# Altium-Sheet_1_2023-12-20.net
KiCad netlist of a schematic drawn in Altium Designer
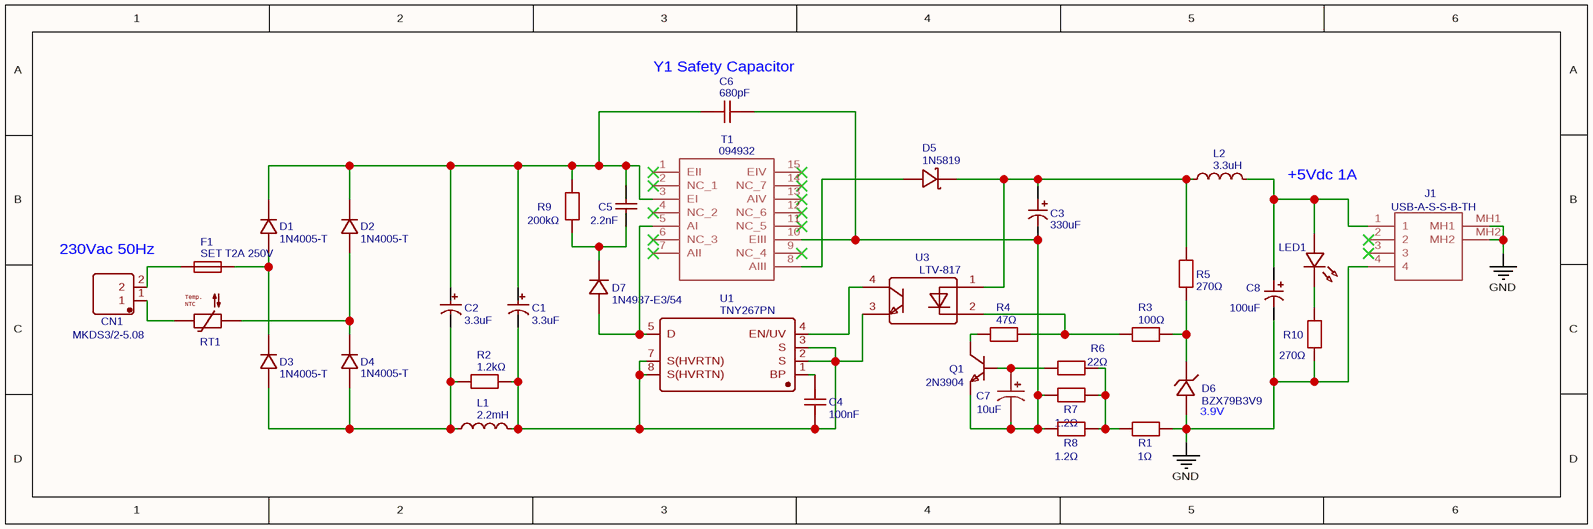
[diagram p0: Altium-Sheet_1_2023-12-20.schdoc]

(export (version "E")
  (design (tool "Eeschema 10.0.6"))
  (components
    (comp (ref "C1")
      (value "3.3uF")
      (fields
        (field (name "MANUFACTURER") "CX(承兴)")
        (field (name "MANUFACTURER PART") "KM335M400F12RR0VH2FP0")
      )
      (libsource (lib "altium-import") (part "root_3_3.3uF_"))
    )
    (comp (ref "C2")
      (value "3.3uF")
      (fields
        (field (name "MANUFACTURER") "CX(承兴)")
        (field (name "MANUFACTURER PART") "KM335M400F12RR0VH2FP0")
      )
      (libsource (lib "altium-import") (part "root_3_3.3uF_"))
    )
    (comp (ref "C3")
      (value "330uF")
      (fields
        (field (name "MANUFACTURER") "PANASONIC(松下)")
        (field (name "MANUFACTURER PART") "EEU-FM1V331")
        (field (name "CONTRIBUTOR") "lcsc")
      )
      (libsource (lib "altium-import") (part "root_3_330uF_"))
    )
    (comp (ref "C4")
      (value "100nF")
      (fields
        (field (name "MANUFACTURER") "KNSCHA(科尼盛)")
        (field (name "MANUFACTURER PART") "178MU0002")
        (field (name "CONTRIBUTOR") "lcsc")
      )
      (libsource (lib "altium-import") (part "root_1_100nF_"))
    )
    (comp (ref "C5") (value "2.2nF") (libsource (lib "altium-import") (part "root_1_2.2nF_")))
    (comp (ref "C6")
      (value "680pF")
      (fields
        (field (name "MANUFACTURER") "VISHAY(威世)")
        (field (name "MANUFACTURER PART") "AY1222M47Y5UC63L0")
        (field (name "CONTRIBUTOR") "LCSC")
      )
      (libsource (lib "altium-import") (part "root_0_680pF_"))
    )
    (comp (ref "C7")
      (value "10uF")
      (fields
        (field (name "MANUFACTURER") "rubycon(红宝石)")
        (field (name "MANUFACTURER PART") "10MS510MEFC4X5")
        (field (name "CONTRIBUTOR") "lcsc")
      )
      (libsource (lib "altium-import") (part "root_3_10uF_"))
    )
    (comp (ref "C8")
      (value "100uF")
      (fields
        (field (name "MANUFACTURER") "ELNA(伊娜)")
        (field (name "MANUFACTURER PART") "RFO-25V101MF3P#-T58")
        (field (name "CONTRIBUTOR") "lcsc")
      )
      (libsource (lib "altium-import") (part "root_3_100uF_"))
    )
    (comp (ref "CN1")
      (value "MKDS3/2-5.08")
      (fields
        (field (name "MANUFACTURER") "Phoenix Contact(菲尼克斯)")
        (field (name "MANUFACTURER PART") "1711725")
      )
      (libsource (lib "altium-import") (part "root_2_MKDS3/2-5.08_"))
    )
    (comp (ref "D1")
      (value "1N4005-T")
      (fields (field (name "MANUFACTURER") "DIODES(美台)") (field (name "CONTRIBUTOR") "LCSC"))
      (libsource (lib "altium-import") (part "root_3_1N4005-T_"))
    )
    (comp (ref "D2")
      (value "1N4005-T")
      (fields (field (name "MANUFACTURER") "DIODES(美台)") (field (name "CONTRIBUTOR") "LCSC"))
      (libsource (lib "altium-import") (part "root_3_1N4005-T_"))
    )
    (comp (ref "D3")
      (value "1N4005-T")
      (fields (field (name "MANUFACTURER") "DIODES(美台)") (field (name "CONTRIBUTOR") "LCSC"))
      (libsource (lib "altium-import") (part "root_3_1N4005-T_"))
    )
    (comp (ref "D4")
      (value "1N4005-T")
      (fields (field (name "MANUFACTURER") "DIODES(美台)") (field (name "CONTRIBUTOR") "LCSC"))
      (libsource (lib "altium-import") (part "root_3_1N4005-T_"))
    )
    (comp (ref "D5")
      (value "1N5819")
      (fields (field (name "MANUFACTURER") "ST(意法半导体)"))
      (libsource (lib "altium-import") (part "root_2_1N5819_"))
    )
    (comp (ref "D6")
      (value "BZX79B3V9")
      (fields
        (field (name "MANUFACTURER") "onsemi(安森美)")
        (field (name "MANUFACTURER PART") "1N5921BG")
        (field (name "CONTRIBUTOR") "LCSC")
      )
      (libsource (lib "altium-import") (part "root_0_BZX79B3V9_"))
    )
    (comp (ref "D7")
      (value "1N4937-E3/54")
      (fields (field (name "MANUFACTURER") "VISHAY(威世)") (field (name "CONTRIBUTOR") "LCSC"))
      (libsource (lib "altium-import") (part "root_1_1N4937-E3/54_"))
    )
    (comp (ref "F1")
      (value "SET T2A 250V")
      (fields (field (name "MANUFACTURER") "CHEVRON(诚润电子）") (field (name "CONTRIBUTOR") "lcsc"))
      (libsource (lib "altium-import") (part "root_0_SET T2A 250V_"))
    )
    (comp (ref "J1")
      (value "USB-A-S-S-B-TH")
      (fields (field (name "CONTRIBUTOR") "andreafato"))
      (libsource (lib "altium-import") (part "root_0_USB-A-S-S-B-TH_"))
    )
    (comp (ref "L1")
      (value "2.2mH")
      (fields
        (field (name "MANUFACTURER") "PROD(谱罗德)")
        (field (name "MANUFACTURER PART") "PDPTAT0810-222K")
        (field (name "CONTRIBUTOR") "lcsc")
      )
      (libsource (lib "altium-import") (part "root_0_2.2mH_"))
    )
    (comp (ref "L2")
      (value "3.3uH")
      (fields (field (name "MANUFACTURER PART") "VLU1012-3R3MB") (field (name "CONTRIBUTOR") "LCSC"))
      (libsource (lib "altium-import") (part "root_0_3.3uH_"))
    )
    (comp (ref "LED1")
      (value "LED-TH-5mm_WHT")
      (fields (field (name "CONTRIBUTOR") "LCEDA_Lib"))
      (libsource (lib "altium-import") (part "root_3_LED-TH-5mm_WHT_"))
    )
    (comp (ref "Q1")
      (value "2N3904")
      (fields (field (name "MANUFACTURER") "JSMSEMI(杰盛微)") (field (name "CONTRIBUTOR") "LCSC"))
      (libsource (lib "altium-import") (part "root_0_2N3904_"))
    )
    (comp (ref "R1")
      (value "1Ω")
      (fields
        (field (name "MANUFACTURER") "Tyohm(幸亚电阻)")
        (field (name "MANUFACTURER PART") "RN1/2WS1RFT/B")
        (field (name "CONTRIBUTOR") "lcsc")
      )
      (libsource (lib "altium-import") (part "root_0_1Ω_"))
    )
    (comp (ref "R2")
      (value "1.2kΩ")
      (fields
        (field (name "MANUFACTURER") "VO(翔胜)")
        (field (name "MANUFACTURER PART") "CR1W-1K2±5%-6T63")
        (field (name "CONTRIBUTOR") "lcsc")
      )
      (libsource (lib "altium-import") (part "root_0_1.2kΩ_"))
    )
    (comp (ref "R3")
      (value "100Ω")
      (fields
        (field (name "MANUFACTURER") "VO(翔胜)")
        (field (name "MANUFACTURER PART") "CR1/4W-100Ω±5%-ST52")
        (field (name "CONTRIBUTOR") "lcsc")
      )
      (libsource (lib "altium-import") (part "root_0_100Ω_"))
    )
    (comp (ref "R4")
      (value "47Ω")
      (fields
        (field (name "MANUFACTURER") "VO(翔胜)")
        (field (name "MANUFACTURER PART") "CR1/4W-100Ω±5%-ST52")
        (field (name "CONTRIBUTOR") "lcsc")
      )
      (libsource (lib "altium-import") (part "root_2_47Ω_"))
    )
    (comp (ref "R5")
      (value "270Ω")
      (fields
        (field (name "MANUFACTURER") "VO(翔胜)")
        (field (name "MANUFACTURER PART") "CR1/4W-100Ω±5%-ST52")
        (field (name "CONTRIBUTOR") "lcsc")
      )
      (libsource (lib "altium-import") (part "root_3_270Ω_"))
    )
    (comp (ref "R6")
      (value "22Ω")
      (fields
        (field (name "MANUFACTURER") "VO(翔胜)")
        (field (name "MANUFACTURER PART") "CR1/4W-100Ω±5%-ST52")
        (field (name "CONTRIBUTOR") "lcsc")
      )
      (libsource (lib "altium-import") (part "root_0_22Ω_"))
    )
    (comp (ref "R7")
      (value "1.2Ω")
      (fields
        (field (name "MANUFACTURER") "YAGEO(国巨)")
        (field (name "MANUFACTURER PART") "MFR50SFTE52-1R21")
        (field (name "CONTRIBUTOR") "lcsc")
      )
      (libsource (lib "altium-import") (part "root_0_1.2Ω_"))
    )
    (comp (ref "R8")
      (value "1.2Ω")
      (fields
        (field (name "MANUFACTURER") "YAGEO(国巨)")
        (field (name "MANUFACTURER PART") "MFR50SFTE52-1R21")
        (field (name "CONTRIBUTOR") "lcsc")
      )
      (libsource (lib "altium-import") (part "root_0_1.2Ω_"))
    )
    (comp (ref "R9")
      (value "200kΩ")
      (fields
        (field (name "MANUFACTURER") "VO(翔胜)")
        (field (name "MANUFACTURER PART") "CR1/2W-220K±5%-XT52")
        (field (name "CONTRIBUTOR") "lcsc")
      )
      (libsource (lib "altium-import") (part "root_3_200kΩ_"))
    )
    (comp (ref "R10")
      (value "270Ω")
      (fields
        (field (name "MANUFACTURER") "VO(翔胜)")
        (field (name "MANUFACTURER PART") "CR1/4W-100Ω±5%-ST52")
        (field (name "CONTRIBUTOR") "lcsc")
      )
      (libsource (lib "altium-import") (part "root_3_270Ω_"))
    )
    (comp (ref "RT1")
      (value "NO")
      (fields
        (field (name "MANUFACTURER PART") "CL-120")
        (field (name "MANUFACTURER") "Amphenol Advanced Sensors")
        (field (name "CONTRIBUTOR") "Xperia BlueStacks")
      )
      (libsource (lib "altium-import") (part "root_0_NO_"))
    )
    (comp (ref "T1")
      (value "094932")
      (fields (field (name "CONTRIBUTOR") "andreafato"))
      (libsource (lib "altium-import") (part "root_0_094932_"))
    )
    (comp (ref "U1")
      (value "TNY267PN")
      (fields (field (name "MANUFACTURER") "Power Integrations(帕沃英蒂格盛)"))
      (libsource (lib "altium-import") (part "root_2_TNY267PN_"))
    )
    (comp (ref "U3")
      (value "LTV-817")
      (fields (field (name "MANUFACTURER") "LITEON(光宝)") (field (name "CONTRIBUTOR") "LCSC"))
      (libsource (lib "altium-import") (part "root_0_LTV-817_"))
    )
  )
  (nets
    (net (code "1") (name "GND") (class "Default")
      (node (ref "C8") (pin "2") (pinfunction "2_2") (pintype "passive"))
      (node (ref "D6") (pin "2") (pinfunction "A_2") (pintype "passive"))
      (node (ref "J1") (pin "4") (pinfunction "4_4") (pintype "passive"))
      (node (ref "J1") (pin "MH1") (pinfunction "MH1_MH1") (pintype "passive"))
      (node (ref "J1") (pin "MH2") (pinfunction "MH2_MH2") (pintype "passive"))
      (node (ref "R1") (pin "2") (pinfunction "2_2") (pintype "passive"))
      (node (ref "R10") (pin "2") (pinfunction "2_2") (pintype "passive"))
    )
    (net (code "2") (name "Net-(C1-Pad2)") (class "Default")
      (node (ref "C1") (pin "2") (pinfunction "2_2") (pintype "passive"))
      (node (ref "C4") (pin "1") (pinfunction "1_1") (pintype "passive"))
      (node (ref "L1") (pin "2") (pinfunction "2_2") (pintype "passive"))
      (node (ref "R2") (pin "2") (pinfunction "2_2") (pintype "passive"))
      (node (ref "U1") (pin "2") (pinfunction "S_2") (pintype "passive"))
      (node (ref "U1") (pin "3") (pinfunction "S_3") (pintype "passive"))
      (node (ref "U1") (pin "7") (pinfunction "S(HVRTN)_7") (pintype "passive"))
      (node (ref "U1") (pin "8") (pinfunction "S(HVRTN)_8") (pintype "passive"))
      (node (ref "U3") (pin "3") (pinfunction "3_3") (pintype "passive"))
    )
    (net (code "3") (name "Net-(C2-Pad2)") (class "Default")
      (node (ref "C2") (pin "2") (pinfunction "2_2") (pintype "passive"))
      (node (ref "D3") (pin "2") (pinfunction "2_2") (pintype "passive"))
      (node (ref "D4") (pin "2") (pinfunction "2_2") (pintype "passive"))
      (node (ref "L1") (pin "1") (pinfunction "1_1") (pintype "passive"))
      (node (ref "R2") (pin "1") (pinfunction "1_1") (pintype "passive"))
    )
    (net (code "4") (name "Net-(C8-Pad1)") (class "Default")
      (node (ref "C8") (pin "1") (pinfunction "1_1") (pintype "passive"))
      (node (ref "J1") (pin "1") (pinfunction "1_1") (pintype "passive"))
      (node (ref "L2") (pin "2") (pinfunction "2_2") (pintype "passive"))
      (node (ref "LED1") (pin "1") (pinfunction "1_1") (pintype "passive"))
    )
    (net (code "5") (name "Net-(CN1-Pad1)") (class "Default")
      (node (ref "CN1") (pin "1") (pinfunction "1_1") (pintype "passive"))
      (node (ref "RT1") (pin "1") (pintype "passive"))
    )
    (net (code "6") (name "Net-(CN1-Pad2)") (class "Default")
      (node (ref "CN1") (pin "2") (pinfunction "2_2") (pintype "passive"))
      (node (ref "F1") (pin "1") (pinfunction "1_1") (pintype "passive"))
    )
    (net (code "7") (name "Net-(D1-Pad2)") (class "Default")
      (node (ref "D1") (pin "2") (pinfunction "2_2") (pintype "passive"))
      (node (ref "D3") (pin "1") (pinfunction "1_1") (pintype "passive"))
      (node (ref "F1") (pin "2") (pinfunction "2_2") (pintype "passive"))
    )
    (net (code "8") (name "Net-(D2-Pad2)") (class "Default")
      (node (ref "D2") (pin "2") (pinfunction "2_2") (pintype "passive"))
      (node (ref "D4") (pin "1") (pinfunction "1_1") (pintype "passive"))
      (node (ref "RT1") (pin "2") (pintype "passive"))
    )
    (net (code "9") (name "Net-(D5-A)") (class "Default")
      (node (ref "D5") (pin "1") (pinfunction "A_1") (pintype "passive"))
      (node (ref "T1") (pin "8") (pinfunction "AIII_8") (pintype "passive"))
    )
    (net (code "10") (name "Net-(D5-K)") (class "Default")
      (node (ref "C3") (pin "1") (pinfunction "1_1") (pintype "passive"))
      (node (ref "D5") (pin "2") (pinfunction "K_2") (pintype "passive"))
      (node (ref "L2") (pin "1") (pinfunction "1_1") (pintype "passive"))
      (node (ref "R5") (pin "1") (pinfunction "1_1") (pintype "passive"))
      (node (ref "U3") (pin "1") (pinfunction "1_1") (pintype "passive"))
    )
    (net (code "11") (name "Net-(D6-C)") (class "Default")
      (node (ref "D6") (pin "1") (pinfunction "C_1") (pintype "passive"))
      (node (ref "R3") (pin "2") (pinfunction "2_2") (pintype "passive"))
      (node (ref "R5") (pin "2") (pinfunction "2_2") (pintype "passive"))
    )
    (net (code "12") (name "Net-(D7-A)") (class "Default")
      (node (ref "D7") (pin "1") (pinfunction "A_1") (pintype "passive"))
      (node (ref "T1") (pin "5") (pinfunction "AI_5") (pintype "passive"))
      (node (ref "U1") (pin "5") (pinfunction "D_5") (pintype "passive"))
    )
    (net (code "13") (name "Net-(D7-K)") (class "Default")
      (node (ref "C5") (pin "1") (pinfunction "1_1") (pintype "passive"))
      (node (ref "D7") (pin "2") (pinfunction "K_2") (pintype "passive"))
      (node (ref "R9") (pin "2") (pinfunction "2_2") (pintype "passive"))
    )
    (net (code "14") (name "Net-(LED1-Pad2)") (class "Default")
      (node (ref "LED1") (pin "2") (pinfunction "2_2") (pintype "passive"))
      (node (ref "R10") (pin "1") (pinfunction "1_1") (pintype "passive"))
    )
    (net (code "15") (name "Net-(Q1-B)") (class "Default")
      (node (ref "C7") (pin "1") (pinfunction "1_1") (pintype "passive"))
      (node (ref "Q1") (pin "2") (pinfunction "B_2") (pintype "passive"))
      (node (ref "R6") (pin "1") (pinfunction "1_1") (pintype "passive"))
    )
    (net (code "16") (name "Net-(Q1-C)") (class "Default")
      (node (ref "Q1") (pin "3") (pinfunction "C_3") (pintype "passive"))
      (node (ref "R4") (pin "2") (pinfunction "2_2") (pintype "passive"))
    )
    (net (code "17") (name "Net-(Q1-E)") (class "Default")
      (node (ref "C3") (pin "2") (pinfunction "2_2") (pintype "passive"))
      (node (ref "C6") (pin "2") (pinfunction "2_2") (pintype "passive"))
      (node (ref "C7") (pin "2") (pinfunction "2_2") (pintype "passive"))
      (node (ref "Q1") (pin "1") (pinfunction "E_1") (pintype "passive"))
      (node (ref "R7") (pin "1") (pinfunction "1_1") (pintype "passive"))
      (node (ref "R8") (pin "1") (pinfunction "1_1") (pintype "passive"))
      (node (ref "T1") (pin "10") (pinfunction "EIII_10") (pintype "passive"))
    )
    (net (code "18") (name "Net-(R1-Pad1)") (class "Default")
      (node (ref "R1") (pin "1") (pinfunction "1_1") (pintype "passive"))
      (node (ref "R6") (pin "2") (pinfunction "2_2") (pintype "passive"))
      (node (ref "R7") (pin "2") (pinfunction "2_2") (pintype "passive"))
      (node (ref "R8") (pin "2") (pinfunction "2_2") (pintype "passive"))
    )
    (net (code "19") (name "Net-(R3-Pad1)") (class "Default")
      (node (ref "R3") (pin "1") (pinfunction "1_1") (pintype "passive"))
      (node (ref "R4") (pin "1") (pinfunction "1_1") (pintype "passive"))
      (node (ref "U3") (pin "2") (pinfunction "2_2") (pintype "passive"))
    )
    (net (code "20") (name "Net-(T1-EI)") (class "Default")
      (node (ref "C1") (pin "1") (pinfunction "1_1") (pintype "passive"))
      (node (ref "C2") (pin "1") (pinfunction "1_1") (pintype "passive"))
      (node (ref "C5") (pin "2") (pinfunction "2_2") (pintype "passive"))
      (node (ref "C6") (pin "1") (pinfunction "1_1") (pintype "passive"))
      (node (ref "D1") (pin "1") (pinfunction "1_1") (pintype "passive"))
      (node (ref "D2") (pin "1") (pinfunction "1_1") (pintype "passive"))
      (node (ref "R9") (pin "1") (pinfunction "1_1") (pintype "passive"))
      (node (ref "T1") (pin "3") (pinfunction "EI_3") (pintype "passive"))
    )
    (net (code "21") (name "Net-(U1-BP)") (class "Default")
      (node (ref "C4") (pin "2") (pinfunction "2_2") (pintype "passive"))
      (node (ref "U1") (pin "1") (pinfunction "BP_1") (pintype "passive"))
    )
    (net (code "22") (name "Net-(U1-EN{slash}UV)") (class "Default")
      (node (ref "U1") (pin "4") (pinfunction "EN/UV_4") (pintype "passive"))
      (node (ref "U3") (pin "4") (pinfunction "4_4") (pintype "passive"))
    )
    (net (code "23") (name "unconnected-(J1-Pad2)") (class "Default")
      (node (ref "J1") (pin "2") (pinfunction "2_2") (pintype "passive+no_connect"))
    )
    (net (code "24") (name "unconnected-(J1-Pad3)") (class "Default")
      (node (ref "J1") (pin "3") (pinfunction "3_3") (pintype "passive+no_connect"))
    )
    (net (code "25") (name "unconnected-(T1-AII-Pad7)") (class "Default")
      (node (ref "T1") (pin "7") (pinfunction "AII_7") (pintype "passive+no_connect"))
    )
    (net (code "26") (name "unconnected-(T1-AIV-Pad13)") (class "Default")
      (node (ref "T1") (pin "13") (pinfunction "AIV_13") (pintype "passive+no_connect"))
    )
    (net (code "27") (name "unconnected-(T1-EII-Pad1)") (class "Default")
      (node (ref "T1") (pin "1") (pinfunction "EII_1") (pintype "passive+no_connect"))
    )
    (net (code "28") (name "unconnected-(T1-EIV-Pad15)") (class "Default")
      (node (ref "T1") (pin "15") (pinfunction "EIV_15") (pintype "passive+no_connect"))
    )
    (net (code "29") (name "unconnected-(T1-NC_1-Pad2)") (class "Default")
      (node (ref "T1") (pin "2") (pinfunction "NC_1_2") (pintype "passive+no_connect"))
    )
    (net (code "30") (name "unconnected-(T1-NC_2-Pad4)") (class "Default")
      (node (ref "T1") (pin "4") (pinfunction "NC_2_4") (pintype "passive+no_connect"))
    )
    (net (code "31") (name "unconnected-(T1-NC_3-Pad6)") (class "Default")
      (node (ref "T1") (pin "6") (pinfunction "NC_3_6") (pintype "passive+no_connect"))
    )
    (net (code "32") (name "unconnected-(T1-NC_4-Pad9)") (class "Default")
      (node (ref "T1") (pin "9") (pinfunction "NC_4_9") (pintype "passive+no_connect"))
    )
    (net (code "33") (name "unconnected-(T1-NC_5-Pad11)") (class "Default")
      (node (ref "T1") (pin "11") (pinfunction "NC_5_11") (pintype "passive+no_connect"))
    )
    (net (code "34") (name "unconnected-(T1-NC_6-Pad12)") (class "Default")
      (node (ref "T1") (pin "12") (pinfunction "NC_6_12") (pintype "passive+no_connect"))
    )
    (net (code "35") (name "unconnected-(T1-NC_7-Pad14)") (class "Default")
      (node (ref "T1") (pin "14") (pinfunction "NC_7_14") (pintype "passive+no_connect"))
    )
  )
)
